# SH3_-_SENSORS.net
KiCad netlist of a schematic drawn in Altium Designer
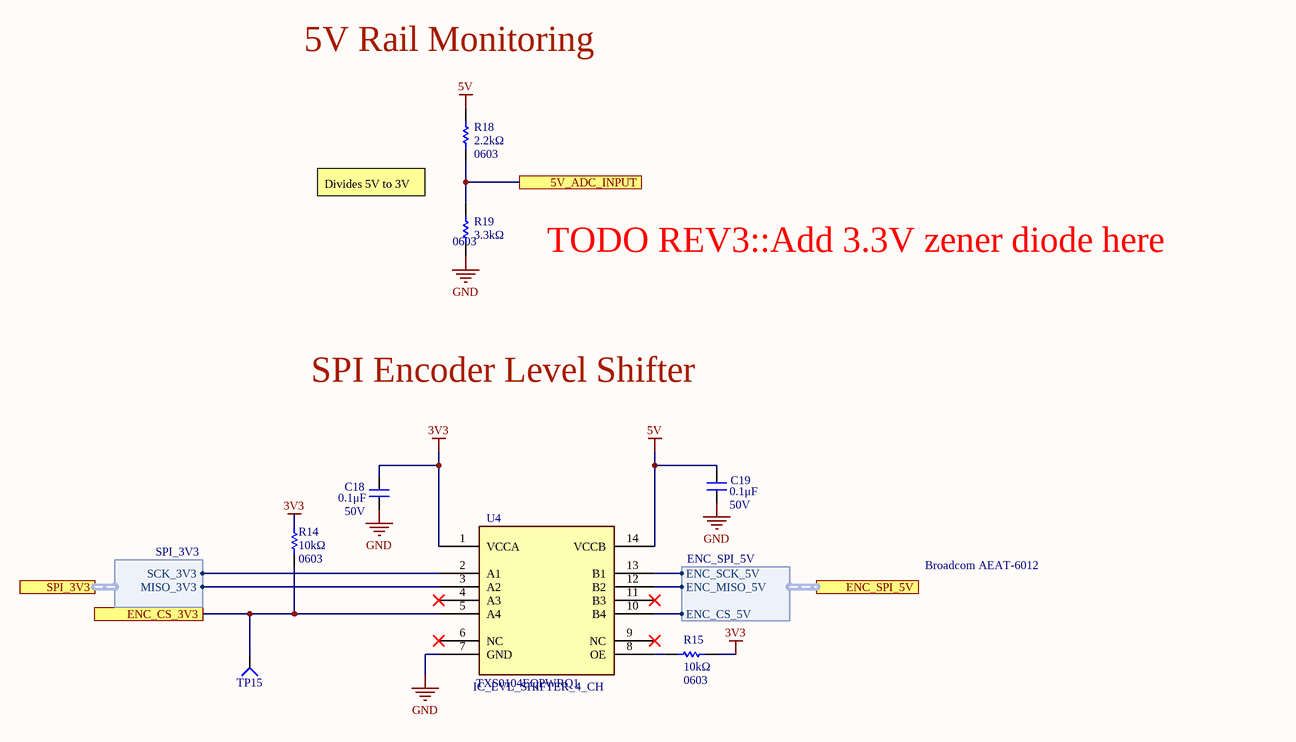
[diagram p0: SH3 - SENSORS.SchDoc]

(export (version "E")
  (design (tool "Eeschema 10.0.6"))
  (components
    (comp (ref "C18")
      (value "0.1μF")
      (footprint "CAP0603")
      (description "CAP CER 0.1UF 50V X7R 0603")
      (fields (field (name "VOLTAGE RATING") "50V") (field (name "Comment") "CAP_0.1uF_50V_0603"))
      (libsource (lib "UWRT_Schematic_Library_2020") (part "CAP_0.1uF_50V_0603"))
    )
    (comp (ref "C19")
      (value "0.1μF")
      (footprint "CAP0603")
      (description "CAP CER 0.1UF 50V X7R 0603")
      (fields (field (name "VOLTAGE RATING") "50V") (field (name "Comment") "CAP_0.1uF_50V_0603"))
      (libsource (lib "UWRT_Schematic_Library_2020") (part "CAP_0.1uF_50V_0603"))
    )
    (comp (ref "R14")
      (value "10kΩ")
      (footprint "RESC0603")
      (description "RES 10K OHM 5% 1/10W 0603")
      (fields
        (field (name "TOLERANCE") "5%")
        (field (name "PACKAGE/FOOTPRINT") "0603")
        (field (name "Comment") "RES_10kΩ_0603_5%")
      )
      (libsource (lib "UWRT_Schematic_Library_2020") (part "RES_10kΩ_0603_5%"))
    )
    (comp (ref "R15")
      (value "10kΩ")
      (footprint "RESC0603")
      (description "RES 10K OHM 5% 1/10W 0603")
      (fields
        (field (name "TOLERANCE") "5%")
        (field (name "PACKAGE/FOOTPRINT") "0603")
        (field (name "Comment") "RES_10kΩ_0603_5%")
      )
      (libsource (lib "UWRT_Schematic_Library_2020") (part "RES_10kΩ_0603_5%"))
    )
    (comp (ref "R18")
      (value "2.2kΩ")
      (footprint "RESC0603")
      (description "RES 2.2K OHM 1% 1/10W 0603")
      (fields
        (field (name "TOLERANCE") "1%")
        (field (name "PACKAGE/FOOTPRINT") "0603")
        (field (name "Comment") "RES_2.2kΩ_0603_1%")
      )
      (libsource (lib "UWRT_Schematic_Library_2020") (part "RES_2.2kΩ_0603_1%"))
    )
    (comp (ref "R19")
      (value "3.3kΩ")
      (footprint "RESC0603")
      (description "RES 3.3K OHM 1% 1/10W 0603")
      (fields
        (field (name "TOLERANCE") "1%")
        (field (name "PACKAGE/FOOTPRINT") "0603")
        (field (name "Comment") "RES_3.3kΩ_0603_1%")
      )
      (libsource (lib "UWRT_Schematic_Library_2020") (part "RES_3.3kΩ_0603_1%"))
    )
    (comp (ref "TP15")
      (value "TESTPOINT_1MM_CIRCLE")
      (footprint "TESTPOINT_CIRCLE_1MM")
      (description "TESTPOINT 1MM CIRCLE")
      (libsource (lib "UWRT_Schematic_Library_2020") (part "TESTPOINT_1MM_CIRCLE"))
    )
    (comp (ref "U4")
      (value "IC_LVL_SHIFTER_4_CH")
      (footprint "UWRT_Footprint_Library_2020:TXS0104EQPWRQ1")
      (description "IC BIDIRECTIONAL LEVEL SHIFTER 4 CHANNEL 14TSSOP")
      (fields (field (name "MANUFACTURER PART NUMBER 1") "TXS0104EQPWRQ1"))
      (libsource (lib "UWRT_Schematic_Library_2020") (part "IC_LVL_SHIFTER_4_CH"))
    )
  )
  (nets
    (net (code "3") (name "/5V_ADC_INPUT") (class "Default")
      (node (ref "R18") (pin "1") (pinfunction "1_1") (pintype "passive"))
      (node (ref "R19") (pin "2") (pinfunction "2_2") (pintype "passive"))
    )
    (net (code "4") (name "/ENC_CS_3V3") (class "Default")
      (node (ref "R14") (pin "1") (pinfunction "1_1") (pintype "passive"))
      (node (ref "TP15") (pin "1") (pinfunction "=value_1") (pintype "passive"))
      (node (ref "U4") (pin "5") (pinfunction "A4_5") (pintype "passive"))
    )
    (net (code "5") (name "/ENC_CS_5V") (class "Default")
      (node (ref "U4") (pin "10") (pinfunction "B4_10") (pintype "passive"))
    )
    (net (code "6") (name "/ENC_MISO_5V") (class "Default")
      (node (ref "U4") (pin "12") (pinfunction "B2_12") (pintype "passive"))
    )
    (net (code "7") (name "/ENC_SCK_5V") (class "Default")
      (node (ref "U4") (pin "13") (pinfunction "B1_13") (pintype "passive"))
    )
    (net (code "8") (name "/MISO_3V3") (class "Default")
      (node (ref "U4") (pin "3") (pinfunction "A2_3") (pintype "passive"))
    )
    (net (code "9") (name "/SCK_3V3") (class "Default")
      (node (ref "U4") (pin "2") (pinfunction "A1_2") (pintype "passive"))
    )
    (net (code "12") (name "3V3") (class "Default")
      (node (ref "C18") (pin "2") (pinfunction "2_2") (pintype "passive"))
      (node (ref "R14") (pin "2") (pinfunction "2_2") (pintype "passive"))
      (node (ref "R15") (pin "2") (pinfunction "2_2") (pintype "passive"))
      (node (ref "U4") (pin "1") (pinfunction "VCCA_1") (pintype "passive"))
    )
    (net (code "13") (name "5V") (class "Default")
      (node (ref "C19") (pin "2") (pinfunction "2_2") (pintype "passive"))
      (node (ref "R18") (pin "2") (pinfunction "2_2") (pintype "passive"))
      (node (ref "U4") (pin "14") (pinfunction "VCCB_14") (pintype "passive"))
    )
    (net (code "14") (name "GND") (class "Default")
      (node (ref "C18") (pin "1") (pinfunction "1_1") (pintype "passive"))
      (node (ref "C19") (pin "1") (pinfunction "1_1") (pintype "passive"))
      (node (ref "R19") (pin "1") (pinfunction "1_1") (pintype "passive"))
      (node (ref "U4") (pin "7") (pinfunction "GND_7") (pintype "passive"))
    )
    (net (code "15") (name "Net-(U4-OE)") (class "Default")
      (node (ref "R15") (pin "1") (pinfunction "1_1") (pintype "passive"))
      (node (ref "U4") (pin "8") (pinfunction "OE_8") (pintype "passive"))
    )
    (net (code "16") (name "unconnected-(U4-A3-Pad4)") (class "Default")
      (node (ref "U4") (pin "4") (pinfunction "A3_4") (pintype "passive+no_connect"))
    )
    (net (code "17") (name "unconnected-(U4-B3-Pad11)") (class "Default")
      (node (ref "U4") (pin "11") (pinfunction "B3_11") (pintype "passive+no_connect"))
    )
    (net (code "18") (name "unconnected-(U4-NC-Pad6)") (class "Default")
      (node (ref "U4") (pin "6") (pinfunction "NC_6") (pintype "passive+no_connect"))
    )
    (net (code "19") (name "unconnected-(U4-NC-Pad9)") (class "Default")
      (node (ref "U4") (pin "9") (pinfunction "NC_9") (pintype "passive+no_connect"))
    )
  )
)
